# 36soj_bob.net
KiCad netlist of a schematic drawn in EAGLE
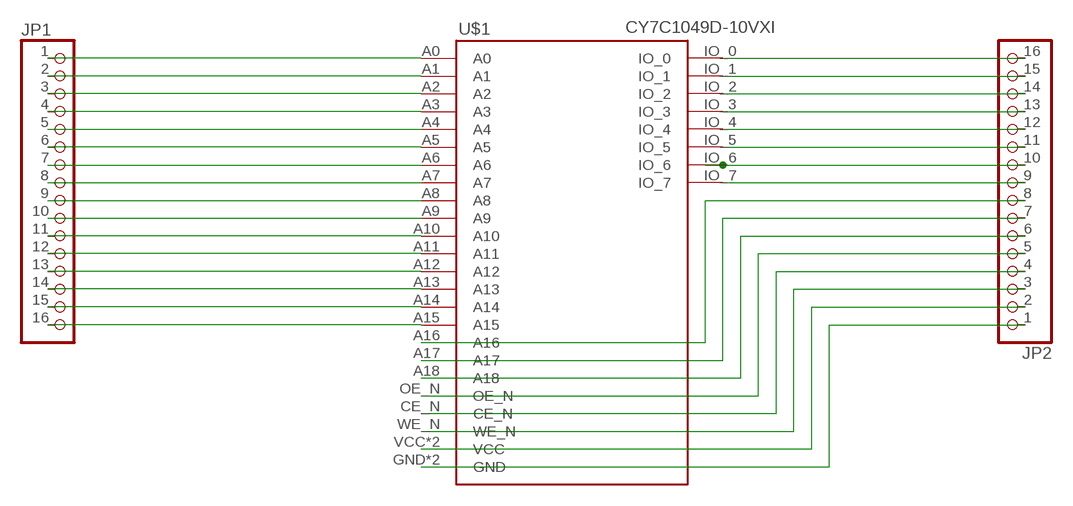
[diagram p0: schematic, sheet 1]

(export (version "E")
  (design (tool "Eeschema 10.0.6"))
  (components
    (comp (ref "JP1")
      (value "PINHD-1X16")
      (footprint "eagle-import:1X16")
      (libsource (lib "eagle-import") (part "PINHD-1X16"))
    )
    (comp (ref "JP2")
      (value "PINHD-1X16")
      (footprint "eagle-import:1X16")
      (libsource (lib "eagle-import") (part "PINHD-1X16"))
    )
    (comp (ref "U$1")
      (value "CY7C1049D-10VXI")
      (footprint "eagle-import:SOJ36")
      (libsource (lib "eagle-import") (part "CY7C1049D-10VXI"))
    )
  )
  (nets
    (net (code "1") (name "Net-(JP1-Pad1)") (class "Default")
      (node (ref "JP1") (pin "1") (pinfunction "1_1") (pintype "passive"))
      (node (ref "U$1") (pin "A0") (pinfunction "A0_A0") (pintype "input"))
    )
    (net (code "2") (name "Net-(JP1-Pad2)") (class "Default")
      (node (ref "JP1") (pin "2") (pinfunction "2_2") (pintype "passive"))
      (node (ref "U$1") (pin "A1") (pinfunction "A1_A1") (pintype "input"))
    )
    (net (code "3") (name "Net-(JP1-Pad3)") (class "Default")
      (node (ref "JP1") (pin "3") (pinfunction "3_3") (pintype "passive"))
      (node (ref "U$1") (pin "A2") (pinfunction "A2_A2") (pintype "input"))
    )
    (net (code "4") (name "Net-(JP1-Pad4)") (class "Default")
      (node (ref "JP1") (pin "4") (pinfunction "4_4") (pintype "passive"))
      (node (ref "U$1") (pin "A3") (pinfunction "A3_A3") (pintype "input"))
    )
    (net (code "5") (name "Net-(JP1-Pad5)") (class "Default")
      (node (ref "JP1") (pin "5") (pinfunction "5_5") (pintype "passive"))
      (node (ref "U$1") (pin "A4") (pinfunction "A4_A4") (pintype "input"))
    )
    (net (code "6") (name "Net-(JP1-Pad6)") (class "Default")
      (node (ref "JP1") (pin "6") (pinfunction "6_6") (pintype "passive"))
      (node (ref "U$1") (pin "A5") (pinfunction "A5_A5") (pintype "input"))
    )
    (net (code "7") (name "Net-(JP1-Pad7)") (class "Default")
      (node (ref "JP1") (pin "7") (pinfunction "7_7") (pintype "passive"))
      (node (ref "U$1") (pin "A6") (pinfunction "A6_A6") (pintype "input"))
    )
    (net (code "8") (name "Net-(JP1-Pad8)") (class "Default")
      (node (ref "JP1") (pin "8") (pinfunction "8_8") (pintype "passive"))
      (node (ref "U$1") (pin "A7") (pinfunction "A7_A7") (pintype "input"))
    )
    (net (code "9") (name "Net-(JP1-Pad9)") (class "Default")
      (node (ref "JP1") (pin "9") (pinfunction "9_9") (pintype "passive"))
      (node (ref "U$1") (pin "A8") (pinfunction "A8_A8") (pintype "input"))
    )
    (net (code "10") (name "Net-(JP1-Pad10)") (class "Default")
      (node (ref "JP1") (pin "10") (pinfunction "10_10") (pintype "passive"))
      (node (ref "U$1") (pin "A9") (pinfunction "A9_A9") (pintype "input"))
    )
    (net (code "11") (name "Net-(JP1-Pad11)") (class "Default")
      (node (ref "JP1") (pin "11") (pinfunction "11_11") (pintype "passive"))
      (node (ref "U$1") (pin "A10") (pinfunction "A10_A10") (pintype "input"))
    )
    (net (code "12") (name "Net-(JP1-Pad12)") (class "Default")
      (node (ref "JP1") (pin "12") (pinfunction "12_12") (pintype "passive"))
      (node (ref "U$1") (pin "A11") (pinfunction "A11_A11") (pintype "input"))
    )
    (net (code "13") (name "Net-(JP1-Pad13)") (class "Default")
      (node (ref "JP1") (pin "13") (pinfunction "13_13") (pintype "passive"))
      (node (ref "U$1") (pin "A12") (pinfunction "A12_A12") (pintype "input"))
    )
    (net (code "14") (name "Net-(JP1-Pad14)") (class "Default")
      (node (ref "JP1") (pin "14") (pinfunction "14_14") (pintype "passive"))
      (node (ref "U$1") (pin "A13") (pinfunction "A13_A13") (pintype "input"))
    )
    (net (code "15") (name "Net-(JP1-Pad15)") (class "Default")
      (node (ref "JP1") (pin "15") (pinfunction "15_15") (pintype "passive"))
      (node (ref "U$1") (pin "A14") (pinfunction "A14_A14") (pintype "input"))
    )
    (net (code "16") (name "Net-(JP1-Pad16)") (class "Default")
      (node (ref "JP1") (pin "16") (pinfunction "16_16") (pintype "passive"))
      (node (ref "U$1") (pin "A15") (pinfunction "A15_A15") (pintype "input"))
    )
    (net (code "17") (name "Net-(JP2-Pad1)") (class "Default")
      (node (ref "JP2") (pin "1") (pinfunction "1_1") (pintype "passive"))
      (node (ref "U$1") (pin "GND") (pinfunction "GND_GND") (pintype "power_in"))
      (node (ref "U$1") (pin "GND_") (pinfunction "GND_GND_") (pintype "power_in"))
    )
    (net (code "18") (name "Net-(JP2-Pad2)") (class "Default")
      (node (ref "JP2") (pin "2") (pinfunction "2_2") (pintype "passive"))
      (node (ref "U$1") (pin "VCC") (pinfunction "VCC_VCC") (pintype "power_in"))
      (node (ref "U$1") (pin "VCC_") (pinfunction "VCC_VCC_") (pintype "power_in"))
    )
    (net (code "19") (name "Net-(JP2-Pad3)") (class "Default")
      (node (ref "JP2") (pin "3") (pinfunction "3_3") (pintype "passive"))
      (node (ref "U$1") (pin "WE_N") (pinfunction "WE_N_WE_N") (pintype "input"))
    )
    (net (code "20") (name "Net-(JP2-Pad4)") (class "Default")
      (node (ref "JP2") (pin "4") (pinfunction "4_4") (pintype "passive"))
      (node (ref "U$1") (pin "CE_N") (pinfunction "CE_N_CE_N") (pintype "input"))
    )
    (net (code "21") (name "Net-(JP2-Pad5)") (class "Default")
      (node (ref "JP2") (pin "5") (pinfunction "5_5") (pintype "passive"))
      (node (ref "U$1") (pin "OE_N") (pinfunction "OE_N_OE_N") (pintype "input"))
    )
    (net (code "22") (name "Net-(JP2-Pad6)") (class "Default")
      (node (ref "JP2") (pin "6") (pinfunction "6_6") (pintype "passive"))
      (node (ref "U$1") (pin "A18") (pinfunction "A18_A18") (pintype "input"))
    )
    (net (code "23") (name "Net-(JP2-Pad7)") (class "Default")
      (node (ref "JP2") (pin "7") (pinfunction "7_7") (pintype "passive"))
      (node (ref "U$1") (pin "A17") (pinfunction "A17_A17") (pintype "input"))
    )
    (net (code "24") (name "Net-(JP2-Pad8)") (class "Default")
      (node (ref "JP2") (pin "8") (pinfunction "8_8") (pintype "passive"))
      (node (ref "U$1") (pin "A16") (pinfunction "A16_A16") (pintype "input"))
    )
    (net (code "25") (name "Net-(JP2-Pad9)") (class "Default")
      (node (ref "JP2") (pin "9") (pinfunction "9_9") (pintype "passive"))
      (node (ref "U$1") (pin "IO_7") (pinfunction "IO_7_IO_7") (pintype "bidirectional"))
    )
    (net (code "26") (name "Net-(JP2-Pad10)") (class "Default")
      (node (ref "JP2") (pin "10") (pinfunction "10_10") (pintype "passive"))
      (node (ref "U$1") (pin "IO_6") (pinfunction "IO_6_IO_6") (pintype "bidirectional"))
    )
    (net (code "27") (name "Net-(JP2-Pad11)") (class "Default")
      (node (ref "JP2") (pin "11") (pinfunction "11_11") (pintype "passive"))
      (node (ref "U$1") (pin "IO_5") (pinfunction "IO_5_IO_5") (pintype "bidirectional"))
    )
    (net (code "28") (name "Net-(JP2-Pad12)") (class "Default")
      (node (ref "JP2") (pin "12") (pinfunction "12_12") (pintype "passive"))
      (node (ref "U$1") (pin "IO_4") (pinfunction "IO_4_IO_4") (pintype "bidirectional"))
    )
    (net (code "29") (name "Net-(JP2-Pad13)") (class "Default")
      (node (ref "JP2") (pin "13") (pinfunction "13_13") (pintype "passive"))
      (node (ref "U$1") (pin "IO_3") (pinfunction "IO_3_IO_3") (pintype "bidirectional"))
    )
    (net (code "30") (name "Net-(JP2-Pad14)") (class "Default")
      (node (ref "JP2") (pin "14") (pinfunction "14_14") (pintype "passive"))
      (node (ref "U$1") (pin "IO_2") (pinfunction "IO_2_IO_2") (pintype "bidirectional"))
    )
    (net (code "31") (name "Net-(JP2-Pad15)") (class "Default")
      (node (ref "JP2") (pin "15") (pinfunction "15_15") (pintype "passive"))
      (node (ref "U$1") (pin "IO_1") (pinfunction "IO_1_IO_1") (pintype "bidirectional"))
    )
    (net (code "32") (name "Net-(JP2-Pad16)") (class "Default")
      (node (ref "JP2") (pin "16") (pinfunction "16_16") (pintype "passive"))
      (node (ref "U$1") (pin "IO_0") (pinfunction "IO_0_IO_0") (pintype "bidirectional"))
    )
  )
)
